# DCDC-Converters.net
KiCad netlist of a schematic drawn in Altium Designer
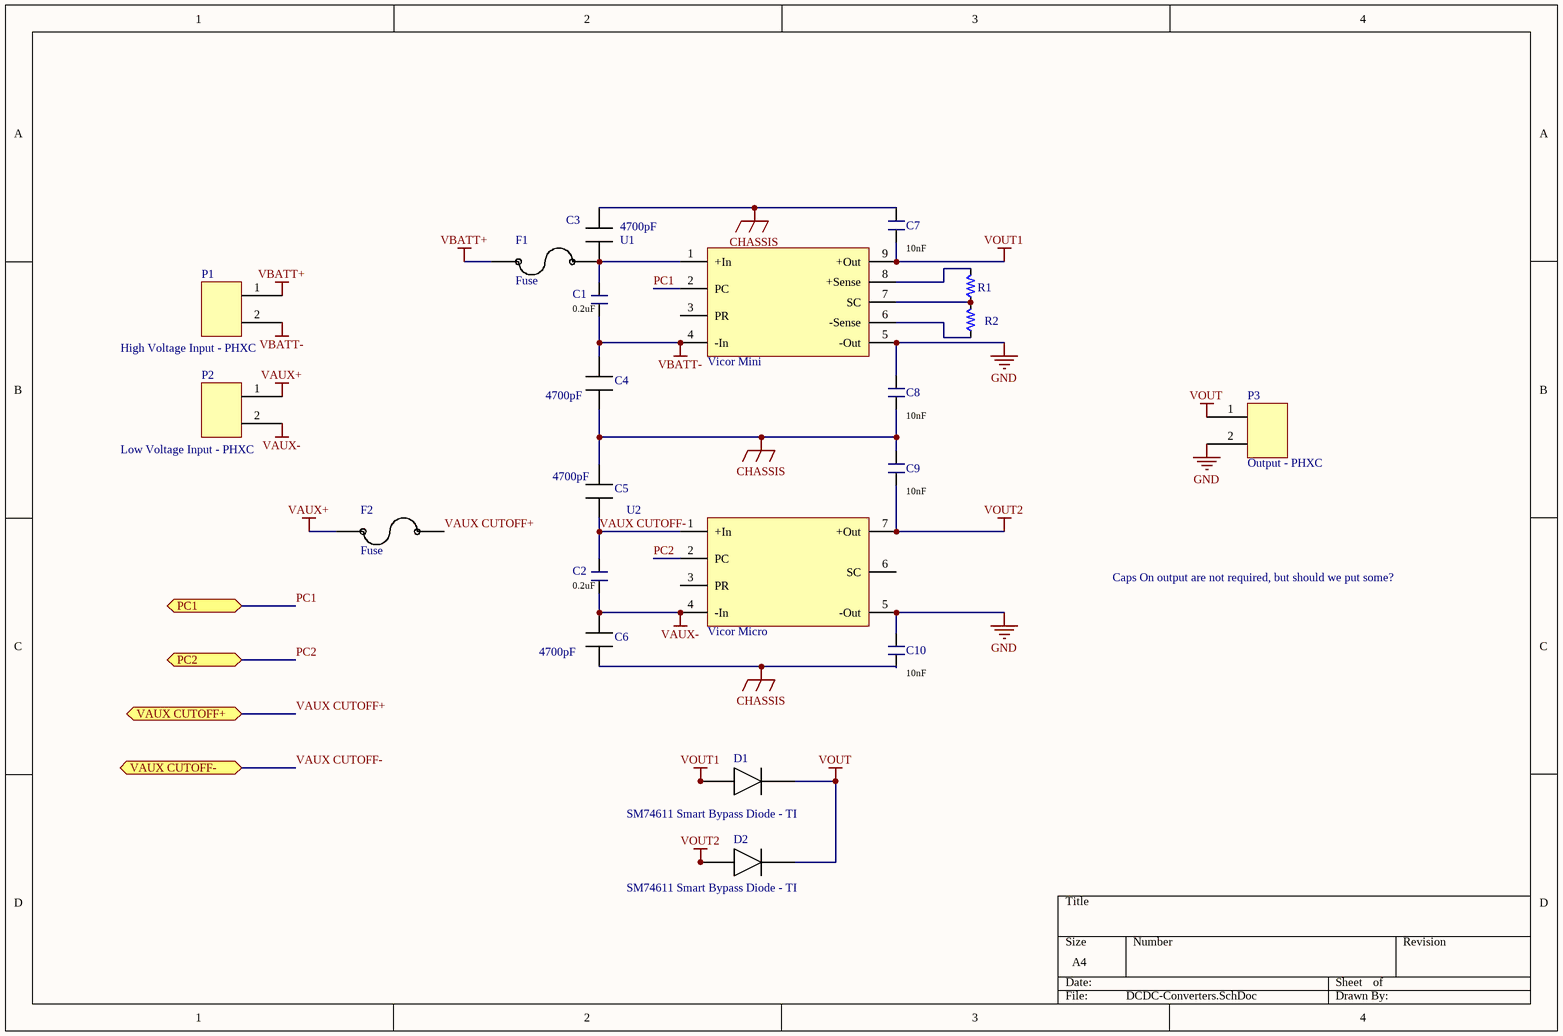
[diagram p0: DCDC-Converters.SchDoc]

(export (version "E")
  (design (tool "Eeschema 10.0.6"))
  (components
    (comp (ref "C1")
      (value "SCH_GENERIC_CAPACITOR_0603")
      (footprint "PCB_GENERIC_SMD_0603")
      (description "Generic SMD capacitor 0603")
      (fields (field (name "TOLERANCE") "*%") (field (name "CAPACITANCE") "0.2uF"))
      (libsource (lib "Generic 0603 Capacitor") (part "SCH_GENERIC_CAPACITOR_0603"))
    )
    (comp (ref "C2")
      (value "SCH_GENERIC_CAPACITOR_0603")
      (footprint "PCB_GENERIC_SMD_0603")
      (description "Generic SMD capacitor 0603")
      (fields (field (name "TOLERANCE") "*%") (field (name "CAPACITANCE") "0.2uF"))
      (libsource (lib "Generic 0603 Capacitor") (part "SCH_GENERIC_CAPACITOR_0603"))
    )
    (comp (ref "C3")
      (value "X1-Y2 Capacitor")
      (fields (field (name "CAPACITANCE") "4700pF"))
      (libsource (lib "Murata 2220 X1-Y2 Capacitor") (part "Murata 2220 X1-Y2 Capacitor"))
    )
    (comp (ref "C4")
      (value "X1-Y2 Capacitor")
      (fields (field (name "CAPACITANCE") "4700pF"))
      (libsource (lib "Murata 2220 X1-Y2 Capacitor") (part "Murata 2220 X1-Y2 Capacitor"))
    )
    (comp (ref "C5")
      (value "X1-Y2 Capacitor")
      (fields (field (name "CAPACITANCE") "4700pF"))
      (libsource (lib "Murata 2220 X1-Y2 Capacitor") (part "Murata 2220 X1-Y2 Capacitor"))
    )
    (comp (ref "C6")
      (value "X1-Y2 Capacitor")
      (fields (field (name "CAPACITANCE") "4700pF"))
      (libsource (lib "Murata 2220 X1-Y2 Capacitor") (part "Murata 2220 X1-Y2 Capacitor"))
    )
    (comp (ref "C7")
      (value "SCH_GENERIC_CAPACITOR_0603")
      (footprint "PCB_GENERIC_SMD_0603")
      (description "Generic SMD capacitor 0603")
      (fields (field (name "TOLERANCE") "*%") (field (name "CAPACITANCE") "10nF"))
      (libsource (lib "Generic 0603 Capacitor") (part "SCH_GENERIC_CAPACITOR_0603"))
    )
    (comp (ref "C8")
      (value "SCH_GENERIC_CAPACITOR_0603")
      (footprint "PCB_GENERIC_SMD_0603")
      (description "Generic SMD capacitor 0603")
      (fields (field (name "TOLERANCE") "*%") (field (name "CAPACITANCE") "10nF"))
      (libsource (lib "Generic 0603 Capacitor") (part "SCH_GENERIC_CAPACITOR_0603"))
    )
    (comp (ref "C9")
      (value "SCH_GENERIC_CAPACITOR_0603")
      (footprint "PCB_GENERIC_SMD_0603")
      (description "Generic SMD capacitor 0603")
      (fields (field (name "TOLERANCE") "*%") (field (name "CAPACITANCE") "10nF"))
      (libsource (lib "Generic 0603 Capacitor") (part "SCH_GENERIC_CAPACITOR_0603"))
    )
    (comp (ref "C10")
      (value "SCH_GENERIC_CAPACITOR_0603")
      (footprint "PCB_GENERIC_SMD_0603")
      (description "Generic SMD capacitor 0603")
      (fields (field (name "TOLERANCE") "*%") (field (name "CAPACITANCE") "10nF"))
      (libsource (lib "Generic 0603 Capacitor") (part "SCH_GENERIC_CAPACITOR_0603"))
    )
    (comp (ref "D1")
      (value "SM74611 Smart Bypass Diode - TI")
      (libsource (lib "SM74611 Smart Bypass Diode - TI") (part "SM74611 Smart Bypass Diode - TI"))
    )
    (comp (ref "D2")
      (value "SM74611 Smart Bypass Diode - TI")
      (libsource (lib "SM74611 Smart Bypass Diode - TI") (part "SM74611 Smart Bypass Diode - TI"))
    )
    (comp (ref "F1") (value "Fuse") (libsource (lib "Fuse Holder") (part "Fuse")))
    (comp (ref "F2") (value "Fuse") (libsource (lib "Fuse Holder") (part "Fuse")))
    (comp (ref "P1")
      (value "High Voltage Input - PHXC")
      (libsource (lib "Phoenix Contact 1720466") (part "Phoenix Contact 1720466"))
    )
    (comp (ref "P2")
      (value "Low Voltage Input - PHXC")
      (libsource (lib "Phoenix Contact 1720466") (part "Phoenix Contact 1720466"))
    )
    (comp (ref "P3") (value "Output - PHXC") (libsource (lib "") (part "Phoenix Contact 1720466_1")))
    (comp (ref "R1")
      (value "SCH_GENERIC_RESISTOR_0603")
      (footprint "PCB_GENERIC_SMD_0603")
      (description "Generic SMD resistor 0603")
      (libsource (lib "Generic 0603 Resistor") (part "SCH_GENERIC_RESISTOR_0603"))
    )
    (comp (ref "R2")
      (value "SCH_GENERIC_RESISTOR_0603")
      (footprint "PCB_GENERIC_SMD_0603")
      (description "Generic SMD resistor 0603")
      (libsource (lib "Generic 0603 Resistor") (part "SCH_GENERIC_RESISTOR_0603"))
    )
    (comp (ref "U1")
      (value "Vicor Mini")
      (footprint "Vicor_Mini")
      (libsource (lib "Vicor_MaxiMiniMicro") (part "Vicor Mini"))
    )
    (comp (ref "U2")
      (value "Vicor Micro")
      (footprint "Vicor_Micro")
      (libsource (lib "Vicor_MaxiMiniMicro") (part "Vicor Micro"))
    )
  )
  (nets
    (net (code "1") (name "/PC1") (class "Default")
      (node (ref "U1") (pin "2") (pinfunction "PC_2") (pintype "passive"))
    )
    (net (code "2") (name "/PC2") (class "Default")
      (node (ref "U2") (pin "2") (pinfunction "PC_2") (pintype "passive"))
    )
    (net (code "3") (name "/VAUX CUTOFF+") (class "Default") (node (ref "F2") (pin "2") (pintype "passive")))
    (net (code "4") (name "/VAUX CUTOFF-") (class "Default")
      (node (ref "C2") (pin "2") (pinfunction "2_2") (pintype "passive"))
      (node (ref "C5") (pin "1") (pintype "passive"))
      (node (ref "U2") (pin "1") (pinfunction "+In_1") (pintype "passive"))
    )
    (net (code "5") (name "CHASSIS") (class "Default")
      (node (ref "C10") (pin "1") (pinfunction "1_1") (pintype "passive"))
      (node (ref "C3") (pin "2") (pintype "passive"))
      (node (ref "C4") (pin "1") (pintype "passive"))
      (node (ref "C5") (pin "2") (pintype "passive"))
      (node (ref "C6") (pin "1") (pintype "passive"))
      (node (ref "C7") (pin "2") (pinfunction "2_2") (pintype "passive"))
      (node (ref "C8") (pin "1") (pinfunction "1_1") (pintype "passive"))
      (node (ref "C9") (pin "2") (pinfunction "2_2") (pintype "passive"))
    )
    (net (code "6") (name "GND") (class "Default")
      (node (ref "C10") (pin "2") (pinfunction "2_2") (pintype "passive"))
      (node (ref "C8") (pin "2") (pinfunction "2_2") (pintype "passive"))
      (node (ref "P3") (pin "2") (pinfunction "2_2") (pintype "passive"))
      (node (ref "U1") (pin "5") (pinfunction "-Out_5") (pintype "passive"))
      (node (ref "U2") (pin "5") (pinfunction "-Out_5") (pintype "passive"))
    )
    (net (code "7") (name "Net-(U1-+In)") (class "Default")
      (node (ref "C1") (pin "2") (pinfunction "2_2") (pintype "passive"))
      (node (ref "C3") (pin "1") (pintype "passive"))
      (node (ref "F1") (pin "2") (pintype "passive"))
      (node (ref "U1") (pin "1") (pinfunction "+In_1") (pintype "passive"))
    )
    (net (code "8") (name "Net-(U1-+Sense)") (class "Default")
      (node (ref "R1") (pin "2") (pinfunction "2_2") (pintype "passive"))
      (node (ref "U1") (pin "8") (pinfunction "+Sense_8") (pintype "passive"))
    )
    (net (code "9") (name "Net-(U1--Sense)") (class "Default")
      (node (ref "R2") (pin "1") (pinfunction "1_1") (pintype "passive"))
      (node (ref "U1") (pin "6") (pinfunction "-Sense_6") (pintype "passive"))
    )
    (net (code "10") (name "Net-(U1-SC)") (class "Default")
      (node (ref "R1") (pin "1") (pinfunction "1_1") (pintype "passive"))
      (node (ref "R2") (pin "2") (pinfunction "2_2") (pintype "passive"))
      (node (ref "U1") (pin "7") (pinfunction "SC_7") (pintype "passive"))
    )
    (net (code "11") (name "VAUX+") (class "Default")
      (node (ref "F2") (pin "1") (pintype "passive"))
      (node (ref "P2") (pin "1") (pinfunction "1_1") (pintype "passive"))
    )
    (net (code "12") (name "VAUX-") (class "Default")
      (node (ref "C2") (pin "1") (pinfunction "1_1") (pintype "passive"))
      (node (ref "C6") (pin "2") (pintype "passive"))
      (node (ref "P2") (pin "2") (pinfunction "2_2") (pintype "passive"))
      (node (ref "U2") (pin "4") (pinfunction "-In_4") (pintype "passive"))
    )
    (net (code "13") (name "VBATT+") (class "Default")
      (node (ref "F1") (pin "1") (pintype "passive"))
      (node (ref "P1") (pin "1") (pinfunction "1_1") (pintype "passive"))
    )
    (net (code "14") (name "VBATT-") (class "Default")
      (node (ref "C1") (pin "1") (pinfunction "1_1") (pintype "passive"))
      (node (ref "C4") (pin "2") (pintype "passive"))
      (node (ref "P1") (pin "2") (pinfunction "2_2") (pintype "passive"))
      (node (ref "U1") (pin "4") (pinfunction "-In_4") (pintype "passive"))
    )
    (net (code "15") (name "VOUT") (class "Default")
      (node (ref "D1") (pin "4") (pintype "passive"))
      (node (ref "D2") (pin "4") (pintype "passive"))
      (node (ref "P3") (pin "1") (pinfunction "1_1") (pintype "passive"))
    )
    (net (code "16") (name "VOUT1") (class "Default")
      (node (ref "C7") (pin "1") (pinfunction "1_1") (pintype "passive"))
      (node (ref "D1") (pin "1") (pintype "passive"))
      (node (ref "D1") (pin "3") (pintype "passive"))
      (node (ref "U1") (pin "9") (pinfunction "+Out_9") (pintype "passive"))
    )
    (net (code "17") (name "VOUT2") (class "Default")
      (node (ref "C9") (pin "1") (pinfunction "1_1") (pintype "passive"))
      (node (ref "D2") (pin "1") (pintype "passive"))
      (node (ref "D2") (pin "3") (pintype "passive"))
      (node (ref "U2") (pin "7") (pinfunction "+Out_7") (pintype "passive"))
    )
    (net (code "18") (name "unconnected-(U1-PR-Pad3)") (class "Default")
      (node (ref "U1") (pin "3") (pinfunction "PR_3") (pintype "passive"))
    )
    (net (code "19") (name "unconnected-(U2-PR-Pad3)") (class "Default")
      (node (ref "U2") (pin "3") (pinfunction "PR_3") (pintype "passive"))
    )
    (net (code "20") (name "unconnected-(U2-SC-Pad6)") (class "Default")
      (node (ref "U2") (pin "6") (pinfunction "SC_6") (pintype "passive"))
    )
  )
)
